# anambe_azul.net
KiCad netlist of a schematic drawn in EAGLE
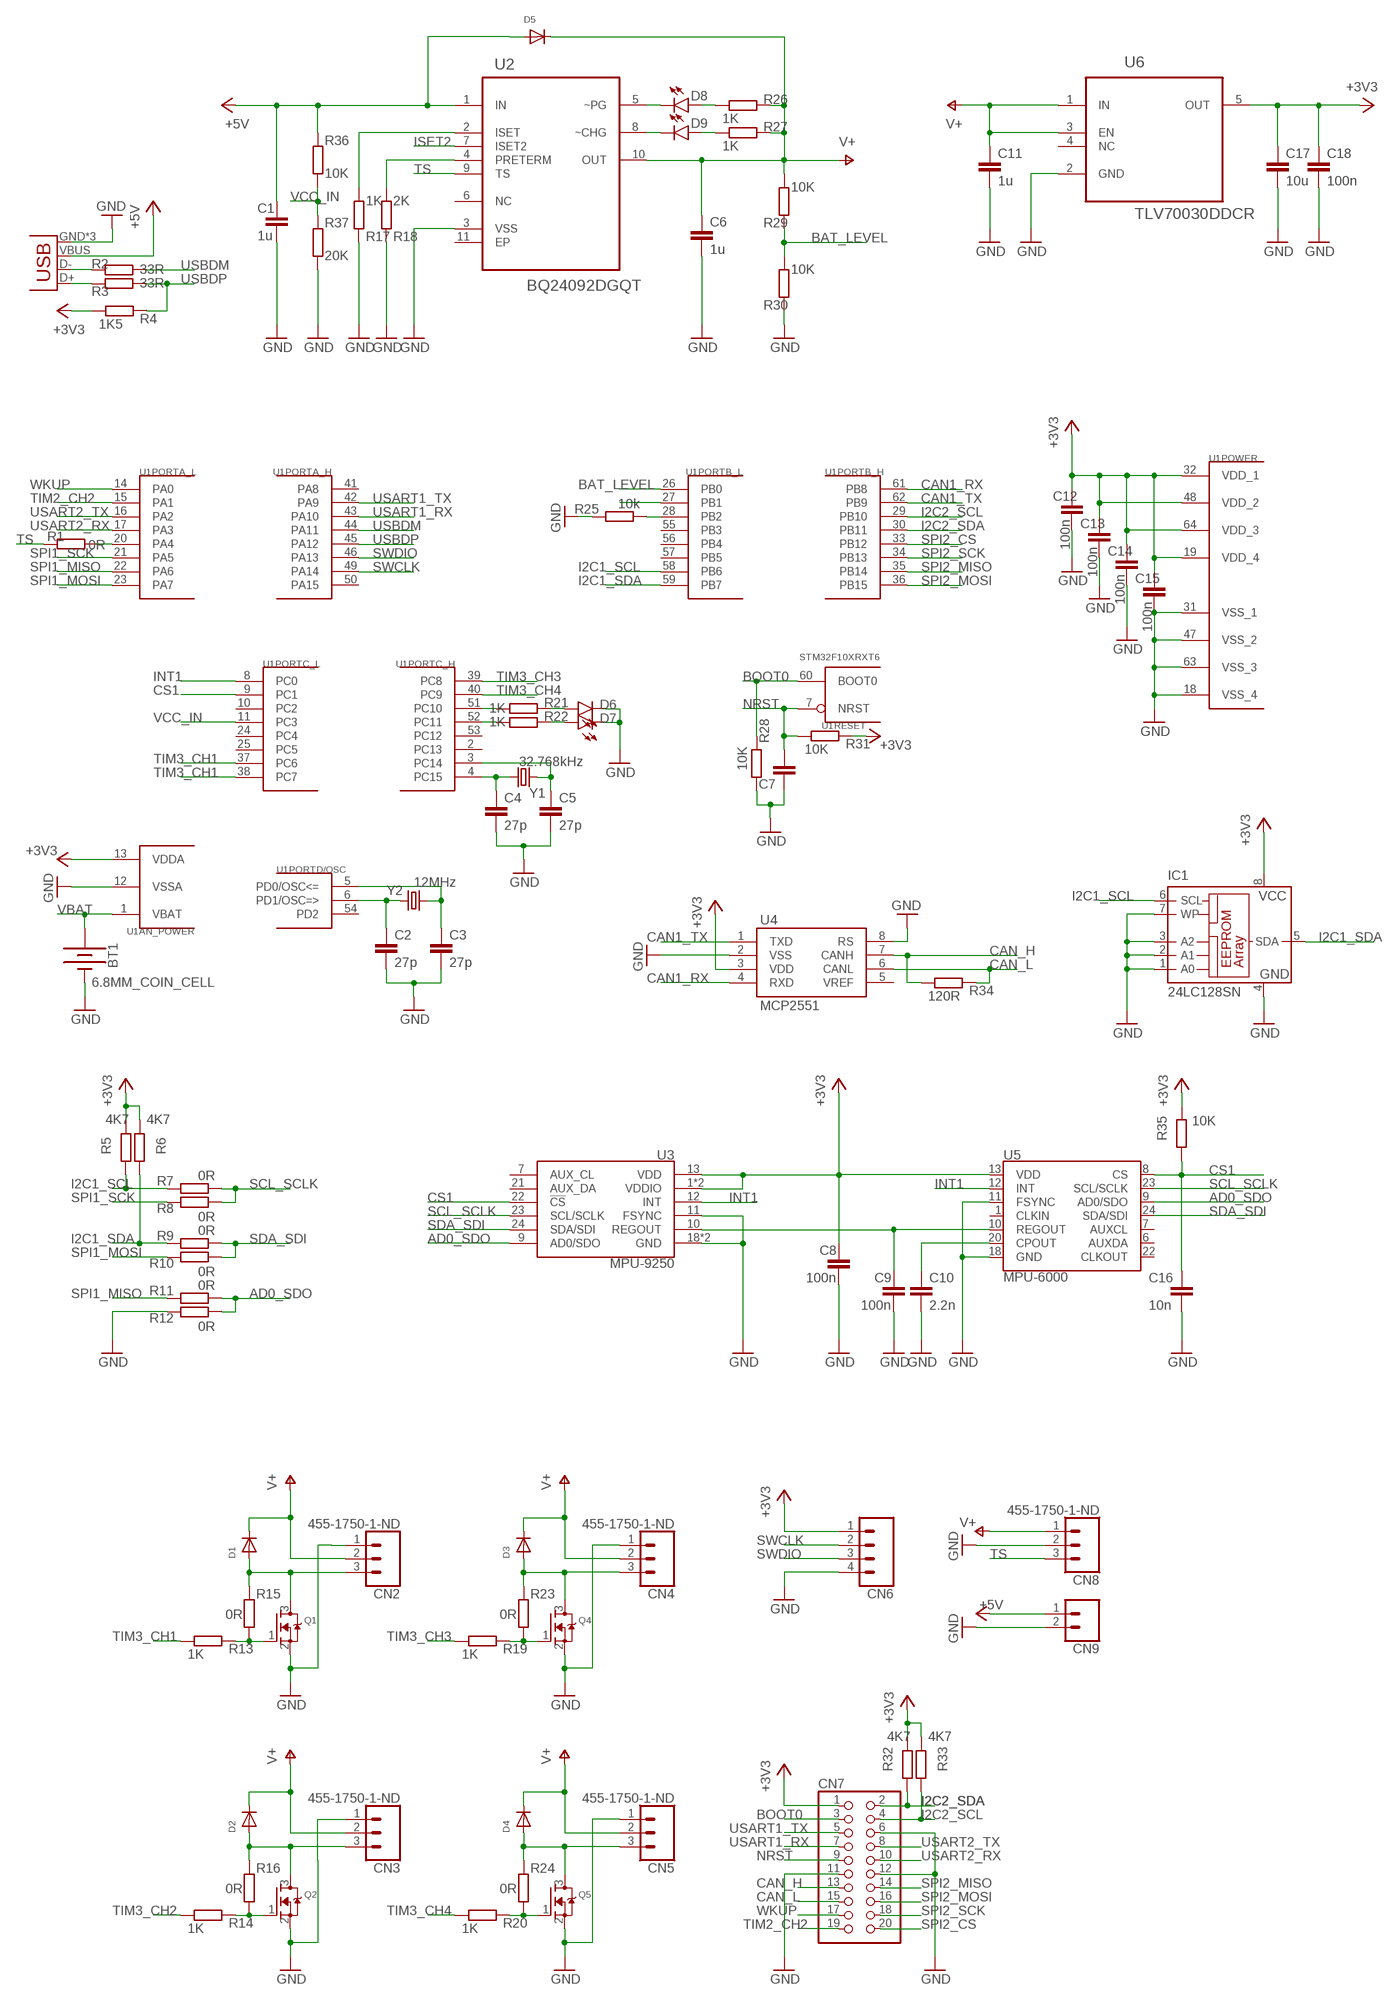
[diagram p0: schematic, sheet 1]

(export (version "E")
  (design (tool "Eeschema 10.0.6"))
  (components
    (comp (ref "BT1")
      (value "6.8MM_COIN_CELL")
      (footprint "eagle-import:BATTCON-6.8MM")
      (libsource (lib "eagle-import") (part "BATTERY-6.8MM_SMD"))
    )
    (comp (ref "C1")
      (value "1u")
      (footprint "eagle-import:C0603")
      (libsource (lib "eagle-import") (part "C-EUC0603"))
    )
    (comp (ref "C2")
      (value "27p")
      (footprint "eagle-import:C0603")
      (libsource (lib "eagle-import") (part "C-EUC0603"))
    )
    (comp (ref "C3")
      (value "27p")
      (footprint "eagle-import:C0603")
      (libsource (lib "eagle-import") (part "C-EUC0603"))
    )
    (comp (ref "C4")
      (value "27p")
      (footprint "eagle-import:C0603")
      (libsource (lib "eagle-import") (part "C-EUC0603"))
    )
    (comp (ref "C5")
      (value "27p")
      (footprint "eagle-import:C0603")
      (libsource (lib "eagle-import") (part "C-EUC0603"))
    )
    (comp (ref "C6")
      (value "1u")
      (footprint "eagle-import:C0603")
      (libsource (lib "eagle-import") (part "C-EUC0603"))
    )
    (comp (ref "C7")
      (value "C-EUC0603")
      (footprint "eagle-import:C0603")
      (libsource (lib "eagle-import") (part "C-EUC0603"))
    )
    (comp (ref "C8")
      (value "100n")
      (footprint "eagle-import:C0603")
      (libsource (lib "eagle-import") (part "C-EUC0603"))
    )
    (comp (ref "C9")
      (value "100n")
      (footprint "eagle-import:C0603")
      (libsource (lib "eagle-import") (part "C-EUC0603"))
    )
    (comp (ref "C10")
      (value "2.2n")
      (footprint "eagle-import:C0603")
      (libsource (lib "eagle-import") (part "C-EUC0603"))
    )
    (comp (ref "C11")
      (value "1u")
      (footprint "eagle-import:C0603")
      (libsource (lib "eagle-import") (part "C-EUC0603"))
    )
    (comp (ref "C12")
      (value "100n")
      (footprint "eagle-import:C0603")
      (libsource (lib "eagle-import") (part "C-EUC0603"))
    )
    (comp (ref "C13")
      (value "100n")
      (footprint "eagle-import:C0603")
      (libsource (lib "eagle-import") (part "C-EUC0603"))
    )
    (comp (ref "C14")
      (value "100n")
      (footprint "eagle-import:C0603")
      (libsource (lib "eagle-import") (part "C-EUC0603"))
    )
    (comp (ref "C15")
      (value "100n")
      (footprint "eagle-import:C0603")
      (libsource (lib "eagle-import") (part "C-EUC0603"))
    )
    (comp (ref "C16")
      (value "10n")
      (footprint "eagle-import:C0603")
      (libsource (lib "eagle-import") (part "C-EUC0603"))
    )
    (comp (ref "C17")
      (value "10u")
      (footprint "eagle-import:C0603")
      (libsource (lib "eagle-import") (part "C-EUC0603"))
    )
    (comp (ref "C18")
      (value "100n")
      (footprint "eagle-import:C0603")
      (libsource (lib "eagle-import") (part "C-EUC0603"))
    )
    (comp (ref "CN1")
      (value "SPARKFUN-CONNECTORS_USB-MICROB")
      (footprint "eagle-import:SPARKFUN-CONNECTORS_USB-MICROB")
      (libsource (lib "eagle-import") (part "SPARKFUN-CONNECTORS_USB-MICROB"))
    )
    (comp (ref "CN2")
      (value "455-1750-1-ND")
      (footprint "eagle-import:1X03")
      (libsource (lib "eagle-import") (part "CONN_03"))
    )
    (comp (ref "CN3")
      (value "455-1750-1-ND")
      (footprint "eagle-import:1X03")
      (libsource (lib "eagle-import") (part "CONN_03"))
    )
    (comp (ref "CN4")
      (value "455-1750-1-ND")
      (footprint "eagle-import:1X03")
      (libsource (lib "eagle-import") (part "CONN_03"))
    )
    (comp (ref "CN5")
      (value "455-1750-1-ND")
      (footprint "eagle-import:1X03")
      (libsource (lib "eagle-import") (part "CONN_03"))
    )
    (comp (ref "CN6")
      (value "CONN_04")
      (footprint "eagle-import:1X04")
      (libsource (lib "eagle-import") (part "CONN_04"))
    )
    (comp (ref "CN7")
      (value "PINHD-2X10")
      (footprint "eagle-import:2X10")
      (libsource (lib "eagle-import") (part "PINHD-2X10"))
    )
    (comp (ref "CN8")
      (value "455-1750-1-ND")
      (footprint "eagle-import:1X03")
      (libsource (lib "eagle-import") (part "CONN_03"))
    )
    (comp (ref "CN9")
      (value "CONN_02")
      (footprint "eagle-import:1X02")
      (libsource (lib "eagle-import") (part "CONN_02"))
    )
    (comp (ref "D1")
      (value "DIODESOD-123")
      (footprint "eagle-import:SOD-123")
      (libsource (lib "eagle-import") (part "DIODESOD-123"))
    )
    (comp (ref "D2")
      (value "DIODESOD-123")
      (footprint "eagle-import:SOD-123")
      (libsource (lib "eagle-import") (part "DIODESOD-123"))
    )
    (comp (ref "D3")
      (value "DIODESOD-123")
      (footprint "eagle-import:SOD-123")
      (libsource (lib "eagle-import") (part "DIODESOD-123"))
    )
    (comp (ref "D4")
      (value "DIODESOD-123")
      (footprint "eagle-import:SOD-123")
      (libsource (lib "eagle-import") (part "DIODESOD-123"))
    )
    (comp (ref "D5")
      (value "DIODESOD-123")
      (footprint "eagle-import:SOD-123")
      (libsource (lib "eagle-import") (part "DIODESOD-123"))
    )
    (comp (ref "D6")
      (value "LED0603")
      (footprint "eagle-import:LED-0603")
      (libsource (lib "eagle-import") (part "LED0603"))
    )
    (comp (ref "D7")
      (value "LED0603")
      (footprint "eagle-import:LED-0603")
      (libsource (lib "eagle-import") (part "LED0603"))
    )
    (comp (ref "D8")
      (value "LED0603")
      (footprint "eagle-import:LED-0603")
      (libsource (lib "eagle-import") (part "LED0603"))
    )
    (comp (ref "D9")
      (value "LED0603")
      (footprint "eagle-import:LED-0603")
      (libsource (lib "eagle-import") (part "LED0603"))
    )
    (comp (ref "IC1")
      (value "24LC128SN")
      (footprint "eagle-import:SO-08")
      (fields (field (name "MF") "MICROCHIP") (field (name "MPN") "24LC128-I/SNG"))
      (libsource (lib "eagle-import") (part "24SNLC128"))
    )
    (comp (ref "Q1")
      (value "MOSFET-NREFLOW")
      (footprint "eagle-import:SOT23")
      (libsource (lib "eagle-import") (part "MOSFET-NREFLOW"))
    )
    (comp (ref "Q2")
      (value "MOSFET-NREFLOW")
      (footprint "eagle-import:SOT23")
      (libsource (lib "eagle-import") (part "MOSFET-NREFLOW"))
    )
    (comp (ref "Q4")
      (value "MOSFET-NREFLOW")
      (footprint "eagle-import:SOT23")
      (libsource (lib "eagle-import") (part "MOSFET-NREFLOW"))
    )
    (comp (ref "Q5")
      (value "MOSFET-NREFLOW")
      (footprint "eagle-import:SOT23")
      (libsource (lib "eagle-import") (part "MOSFET-NREFLOW"))
    )
    (comp (ref "R1")
      (value "0R")
      (footprint "eagle-import:R0603")
      (libsource (lib "eagle-import") (part "R-EU_R0603"))
    )
    (comp (ref "R2")
      (value "33R")
      (footprint "eagle-import:R0603")
      (libsource (lib "eagle-import") (part "R-EU_R0603"))
    )
    (comp (ref "R3")
      (value "33R")
      (footprint "eagle-import:R0603")
      (libsource (lib "eagle-import") (part "R-EU_R0603"))
    )
    (comp (ref "R4")
      (value "1K5")
      (footprint "eagle-import:R0603")
      (libsource (lib "eagle-import") (part "R-EU_R0603"))
    )
    (comp (ref "R5")
      (value "4K7")
      (footprint "eagle-import:R0603")
      (libsource (lib "eagle-import") (part "R-EU_R0603"))
    )
    (comp (ref "R6")
      (value "4K7")
      (footprint "eagle-import:R0603")
      (libsource (lib "eagle-import") (part "R-EU_R0603"))
    )
    (comp (ref "R7")
      (value "0R")
      (footprint "eagle-import:R0603")
      (libsource (lib "eagle-import") (part "R-EU_R0603"))
    )
    (comp (ref "R8")
      (value "0R")
      (footprint "eagle-import:R0603")
      (libsource (lib "eagle-import") (part "R-EU_R0603"))
    )
    (comp (ref "R9")
      (value "0R")
      (footprint "eagle-import:R0603")
      (libsource (lib "eagle-import") (part "R-EU_R0603"))
    )
    (comp (ref "R10")
      (value "0R")
      (footprint "eagle-import:R0603")
      (libsource (lib "eagle-import") (part "R-EU_R0603"))
    )
    (comp (ref "R11")
      (value "0R")
      (footprint "eagle-import:R0603")
      (libsource (lib "eagle-import") (part "R-EU_R0603"))
    )
    (comp (ref "R12")
      (value "0R")
      (footprint "eagle-import:R0603")
      (libsource (lib "eagle-import") (part "R-EU_R0603"))
    )
    (comp (ref "R13")
      (value "1K")
      (footprint "eagle-import:R0603")
      (libsource (lib "eagle-import") (part "R-EU_R0603"))
    )
    (comp (ref "R14")
      (value "1K")
      (footprint "eagle-import:R0603")
      (libsource (lib "eagle-import") (part "R-EU_R0603"))
    )
    (comp (ref "R15")
      (value "0R")
      (footprint "eagle-import:R0603")
      (libsource (lib "eagle-import") (part "R-EU_R0603"))
    )
    (comp (ref "R16")
      (value "0R")
      (footprint "eagle-import:R0603")
      (libsource (lib "eagle-import") (part "R-EU_R0603"))
    )
    (comp (ref "R17")
      (value "1K")
      (footprint "eagle-import:R0603")
      (libsource (lib "eagle-import") (part "R-EU_R0603"))
    )
    (comp (ref "R18")
      (value "2K")
      (footprint "eagle-import:R0603")
      (libsource (lib "eagle-import") (part "R-EU_R0603"))
    )
    (comp (ref "R19")
      (value "1K")
      (footprint "eagle-import:R0603")
      (libsource (lib "eagle-import") (part "R-EU_R0603"))
    )
    (comp (ref "R20")
      (value "1K")
      (footprint "eagle-import:R0603")
      (libsource (lib "eagle-import") (part "R-EU_R0603"))
    )
    (comp (ref "R21")
      (value "1K")
      (footprint "eagle-import:R0603")
      (libsource (lib "eagle-import") (part "R-EU_R0603"))
    )
    (comp (ref "R22")
      (value "1K")
      (footprint "eagle-import:R0603")
      (libsource (lib "eagle-import") (part "R-EU_R0603"))
    )
    (comp (ref "R23")
      (value "0R")
      (footprint "eagle-import:R0603")
      (libsource (lib "eagle-import") (part "R-EU_R0603"))
    )
    (comp (ref "R24")
      (value "0R")
      (footprint "eagle-import:R0603")
      (libsource (lib "eagle-import") (part "R-EU_R0603"))
    )
    (comp (ref "R25")
      (value "10k")
      (footprint "eagle-import:R0603")
      (libsource (lib "eagle-import") (part "R-EU_R0603"))
    )
    (comp (ref "R26")
      (value "1K")
      (footprint "eagle-import:R0603")
      (libsource (lib "eagle-import") (part "R-EU_R0603"))
    )
    (comp (ref "R27")
      (value "1K")
      (footprint "eagle-import:R0603")
      (libsource (lib "eagle-import") (part "R-EU_R0603"))
    )
    (comp (ref "R28")
      (value "10K")
      (footprint "eagle-import:R0603")
      (libsource (lib "eagle-import") (part "R-EU_R0603"))
    )
    (comp (ref "R29")
      (value "10K")
      (footprint "eagle-import:R0603")
      (libsource (lib "eagle-import") (part "R-EU_R0603"))
    )
    (comp (ref "R30")
      (value "10K")
      (footprint "eagle-import:R0603")
      (libsource (lib "eagle-import") (part "R-EU_R0603"))
    )
    (comp (ref "R31")
      (value "10K")
      (footprint "eagle-import:R0603")
      (libsource (lib "eagle-import") (part "R-EU_R0603"))
    )
    (comp (ref "R32")
      (value "4K7")
      (footprint "eagle-import:R0603")
      (libsource (lib "eagle-import") (part "R-EU_R0603"))
    )
    (comp (ref "R33")
      (value "4K7")
      (footprint "eagle-import:R0603")
      (libsource (lib "eagle-import") (part "R-EU_R0603"))
    )
    (comp (ref "R34")
      (value "120R")
      (footprint "eagle-import:R0603")
      (libsource (lib "eagle-import") (part "R-EU_R0603"))
    )
    (comp (ref "R35")
      (value "10K")
      (footprint "eagle-import:R0603")
      (libsource (lib "eagle-import") (part "R-EU_R0603"))
    )
    (comp (ref "R36")
      (value "10K")
      (footprint "eagle-import:R0603")
      (libsource (lib "eagle-import") (part "R-EU_R0603"))
    )
    (comp (ref "R37")
      (value "20K")
      (footprint "eagle-import:R0603")
      (libsource (lib "eagle-import") (part "R-EU_R0603"))
    )
    (comp (ref "U1")
      (value "STM32F10XRXT6")
      (footprint "eagle-import:TQFP64")
      (libsource (lib "eagle-import") (part "STM32F10XRXT6"))
    )
    (comp (ref "U2")
      (value "BQ24092DGQT")
      (footprint "eagle-import:SOP50P490X110-11N")
      (libsource (lib "eagle-import") (part "BQ24092DGQT"))
    )
    (comp (ref "U3")
      (value "MPU-9250")
      (footprint "eagle-import:QFN24-3X3")
      (libsource (lib "eagle-import") (part "MPU-9250"))
    )
    (comp (ref "U4")
      (value "MCP2551")
      (footprint "eagle-import:SO08")
      (libsource (lib "eagle-import") (part "MCP2551"))
    )
    (comp (ref "U5")
      (value "MPU-6000")
      (footprint "eagle-import:QFN-24-EP")
      (libsource (lib "eagle-import") (part "MPU-6000"))
    )
    (comp (ref "U6")
      (value "TLV70030DDCR")
      (footprint "eagle-import:SOT95P280X110-5N")
      (libsource (lib "eagle-import") (part "TLV70030DDCR"))
    )
    (comp (ref "Y1")
      (value "32.768kHz")
      (footprint "eagle-import:CRYSTAL-PTH-2X6-CYL")
      (libsource (lib "eagle-import") (part "CRYSTAL-32.768KHZPTH-2X6"))
    )
    (comp (ref "Y2")
      (value "12MHz")
      (footprint "eagle-import:HC49UP")
      (libsource (lib "eagle-import") (part "CRYSTALHC49UP"))
    )
  )
  (nets
    (net (code "1") (name "+3V3") (class "Default")
      (node (ref "C12") (pin "1") (pinfunction "1_1") (pintype "passive"))
      (node (ref "C13") (pin "1") (pinfunction "1_1") (pintype "passive"))
      (node (ref "C14") (pin "1") (pinfunction "1_1") (pintype "passive"))
      (node (ref "C15") (pin "1") (pinfunction "1_1") (pintype "passive"))
      (node (ref "C17") (pin "1") (pinfunction "1_1") (pintype "passive"))
      (node (ref "C18") (pin "1") (pinfunction "1_1") (pintype "passive"))
      (node (ref "C8") (pin "1") (pinfunction "1_1") (pintype "passive"))
      (node (ref "CN6") (pin "1") (pinfunction "1_1") (pintype "passive"))
      (node (ref "CN7") (pin "1") (pinfunction "1_1") (pintype "passive"))
      (node (ref "IC1") (pin "8") (pinfunction "VCC_8") (pintype "power_in"))
      (node (ref "R31") (pin "2") (pinfunction "2_2") (pintype "passive"))
      (node (ref "R32") (pin "1") (pinfunction "1_1") (pintype "passive"))
      (node (ref "R33") (pin "1") (pinfunction "1_1") (pintype "passive"))
      (node (ref "R35") (pin "2") (pinfunction "2_2") (pintype "passive"))
      (node (ref "R4") (pin "1") (pinfunction "1_1") (pintype "passive"))
      (node (ref "R5") (pin "1") (pinfunction "1_1") (pintype "passive"))
      (node (ref "R6") (pin "1") (pinfunction "1_1") (pintype "passive"))
      (node (ref "U1") (pin "13") (pinfunction "VDDA_13") (pintype "power_in"))
      (node (ref "U1") (pin "19") (pinfunction "VDD_4_19") (pintype "power_in"))
      (node (ref "U1") (pin "32") (pinfunction "VDD_1_32") (pintype "power_in"))
      (node (ref "U1") (pin "48") (pinfunction "VDD_2_48") (pintype "power_in"))
      (node (ref "U1") (pin "64") (pinfunction "VDD_3_64") (pintype "power_in"))
      (node (ref "U3") (pin "1") (pinfunction "VDDIO_1") (pintype "bidirectional"))
      (node (ref "U3") (pin "13") (pinfunction "VDD_13") (pintype "bidirectional"))
      (node (ref "U3") (pin "8") (pinfunction "VDDIO_8") (pintype "bidirectional"))
      (node (ref "U4") (pin "3") (pinfunction "VDD_3") (pintype "bidirectional"))
      (node (ref "U5") (pin "13") (pinfunction "VDD_13") (pintype "bidirectional"))
      (node (ref "U6") (pin "5") (pinfunction "OUT_5") (pintype "output"))
    )
    (net (code "2") (name "+5V") (class "Default")
      (node (ref "C1") (pin "1") (pinfunction "1_1") (pintype "passive"))
      (node (ref "CN1") (pin "VBUS") (pinfunction "VBUS_VBUS") (pintype "bidirectional"))
      (node (ref "CN9") (pin "1") (pinfunction "1_1") (pintype "passive"))
      (node (ref "D5") (pin "A") (pinfunction "A_A") (pintype "passive"))
      (node (ref "R36") (pin "2") (pinfunction "2_2") (pintype "passive"))
      (node (ref "U2") (pin "1") (pinfunction "IN_1") (pintype "power_in"))
    )
    (net (code "3") (name "/AD0_SDO") (class "Default")
      (node (ref "R11") (pin "1") (pinfunction "1_1") (pintype "passive"))
      (node (ref "R12") (pin "1") (pinfunction "1_1") (pintype "passive"))
      (node (ref "U3") (pin "9") (pinfunction "AD0/SDO_9") (pintype "bidirectional"))
      (node (ref "U5") (pin "9") (pinfunction "AD0/SDO_9") (pintype "bidirectional"))
    )
    (net (code "4") (name "/BAT_LEVEL") (class "Default")
      (node (ref "R29") (pin "2") (pinfunction "2_2") (pintype "passive"))
      (node (ref "R30") (pin "1") (pinfunction "1_1") (pintype "passive"))
      (node (ref "U1") (pin "26") (pinfunction "PB0_26") (pintype "bidirectional"))
    )
    (net (code "5") (name "/BOOT0") (class "Default")
      (node (ref "CN7") (pin "3") (pinfunction "3_3") (pintype "passive"))
      (node (ref "R28") (pin "2") (pinfunction "2_2") (pintype "passive"))
      (node (ref "U1") (pin "60") (pinfunction "BOOT0_60") (pintype "input"))
    )
    (net (code "6") (name "/CAN1_RX") (class "Default")
      (node (ref "U1") (pin "61") (pinfunction "PB8_61") (pintype "bidirectional"))
      (node (ref "U4") (pin "4") (pinfunction "RXD_4") (pintype "bidirectional"))
    )
    (net (code "7") (name "/CAN1_TX") (class "Default")
      (node (ref "U1") (pin "62") (pinfunction "PB9_62") (pintype "bidirectional"))
      (node (ref "U4") (pin "1") (pinfunction "TXD_1") (pintype "bidirectional"))
    )
    (net (code "8") (name "/CAN_H") (class "Default")
      (node (ref "CN7") (pin "13") (pinfunction "13_13") (pintype "passive"))
      (node (ref "R34") (pin "1") (pinfunction "1_1") (pintype "passive"))
      (node (ref "U4") (pin "7") (pinfunction "CANH_7") (pintype "bidirectional"))
    )
    (net (code "9") (name "/CAN_L") (class "Default")
      (node (ref "CN7") (pin "15") (pinfunction "15_15") (pintype "passive"))
      (node (ref "R34") (pin "2") (pinfunction "2_2") (pintype "passive"))
      (node (ref "U4") (pin "6") (pinfunction "CANL_6") (pintype "bidirectional"))
    )
    (net (code "10") (name "/CS1") (class "Default")
      (node (ref "C16") (pin "1") (pinfunction "1_1") (pintype "passive"))
      (node (ref "R35") (pin "1") (pinfunction "1_1") (pintype "passive"))
      (node (ref "U1") (pin "9") (pinfunction "PC1_9") (pintype "bidirectional"))
      (node (ref "U3") (pin "22") (pinfunction "~{CS}_22") (pintype "bidirectional"))
      (node (ref "U5") (pin "8") (pinfunction "CS_8") (pintype "bidirectional"))
    )
    (net (code "11") (name "/I2C1_SCL") (class "Default")
      (node (ref "IC1") (pin "6") (pinfunction "SCL_6") (pintype "input"))
      (node (ref "R5") (pin "2") (pinfunction "2_2") (pintype "passive"))
      (node (ref "R7") (pin "2") (pinfunction "2_2") (pintype "passive"))
      (node (ref "U1") (pin "58") (pinfunction "PB6_58") (pintype "bidirectional"))
    )
    (net (code "12") (name "/I2C1_SDA") (class "Default")
      (node (ref "IC1") (pin "5") (pinfunction "SDA_5") (pintype "bidirectional"))
      (node (ref "R6") (pin "2") (pinfunction "2_2") (pintype "passive"))
      (node (ref "R9") (pin "2") (pinfunction "2_2") (pintype "passive"))
      (node (ref "U1") (pin "59") (pinfunction "PB7_59") (pintype "bidirectional"))
    )
    (net (code "13") (name "/I2C2_SCL") (class "Default")
      (node (ref "CN7") (pin "4") (pinfunction "4_4") (pintype "passive"))
      (node (ref "R33") (pin "2") (pinfunction "2_2") (pintype "passive"))
      (node (ref "U1") (pin "29") (pinfunction "PB10_29") (pintype "bidirectional"))
    )
    (net (code "14") (name "/I2C2_SDA") (class "Default")
      (node (ref "CN7") (pin "2") (pinfunction "2_2") (pintype "passive"))
      (node (ref "R32") (pin "2") (pinfunction "2_2") (pintype "passive"))
      (node (ref "U1") (pin "30") (pinfunction "PB11_30") (pintype "bidirectional"))
    )
    (net (code "15") (name "/INT1") (class "Default")
      (node (ref "U1") (pin "8") (pinfunction "PC0_8") (pintype "bidirectional"))
      (node (ref "U3") (pin "12") (pinfunction "INT_12") (pintype "bidirectional"))
      (node (ref "U5") (pin "12") (pinfunction "INT_12") (pintype "bidirectional"))
    )
    (net (code "16") (name "/ISET2") (class "Default")
      (node (ref "U1") (pin "27") (pinfunction "PB1_27") (pintype "bidirectional"))
      (node (ref "U2") (pin "7") (pinfunction "ISET2_7") (pintype "input"))
    )
    (net (code "17") (name "/NRST") (class "Default")
      (node (ref "C7") (pin "2") (pinfunction "2_2") (pintype "passive"))
      (node (ref "CN7") (pin "9") (pinfunction "9_9") (pintype "passive"))
      (node (ref "R31") (pin "1") (pinfunction "1_1") (pintype "passive"))
      (node (ref "U1") (pin "7") (pinfunction "NRST_7") (pintype "input"))
    )
    (net (code "18") (name "/SCL_SCLK") (class "Default")
      (node (ref "R7") (pin "1") (pinfunction "1_1") (pintype "passive"))
      (node (ref "R8") (pin "1") (pinfunction "1_1") (pintype "passive"))
      (node (ref "U3") (pin "23") (pinfunction "SCL/SCLK_23") (pintype "bidirectional"))
      (node (ref "U5") (pin "23") (pinfunction "SCL/SCLK_23") (pintype "bidirectional"))
    )
    (net (code "19") (name "/SDA_SDI") (class "Default")
      (node (ref "R10") (pin "1") (pinfunction "1_1") (pintype "passive"))
      (node (ref "R9") (pin "1") (pinfunction "1_1") (pintype "passive"))
      (node (ref "U3") (pin "24") (pinfunction "SDA/SDI_24") (pintype "bidirectional"))
      (node (ref "U5") (pin "24") (pinfunction "SDA/SDI_24") (pintype "bidirectional"))
    )
    (net (code "20") (name "/SPI1_MISO") (class "Default")
      (node (ref "R11") (pin "2") (pinfunction "2_2") (pintype "passive"))
      (node (ref "U1") (pin "22") (pinfunction "PA6_22") (pintype "bidirectional"))
    )
    (net (code "21") (name "/SPI1_MOSI") (class "Default")
      (node (ref "R10") (pin "2") (pinfunction "2_2") (pintype "passive"))
      (node (ref "U1") (pin "23") (pinfunction "PA7_23") (pintype "bidirectional"))
    )
    (net (code "22") (name "/SPI1_SCK") (class "Default")
      (node (ref "R8") (pin "2") (pinfunction "2_2") (pintype "passive"))
      (node (ref "U1") (pin "21") (pinfunction "PA5_21") (pintype "bidirectional"))
    )
    (net (code "23") (name "/SPI2_CS") (class "Default")
      (node (ref "CN7") (pin "20") (pinfunction "20_20") (pintype "passive"))
      (node (ref "U1") (pin "33") (pinfunction "PB12_33") (pintype "bidirectional"))
    )
    (net (code "24") (name "/SPI2_MISO") (class "Default")
      (node (ref "CN7") (pin "14") (pinfunction "14_14") (pintype "passive"))
      (node (ref "U1") (pin "35") (pinfunction "PB14_35") (pintype "bidirectional"))
    )
    (net (code "25") (name "/SPI2_MOSI") (class "Default")
      (node (ref "CN7") (pin "16") (pinfunction "16_16") (pintype "passive"))
      (node (ref "U1") (pin "36") (pinfunction "PB15_36") (pintype "bidirectional"))
    )
    (net (code "26") (name "/SPI2_SCK") (class "Default")
      (node (ref "CN7") (pin "18") (pinfunction "18_18") (pintype "passive"))
      (node (ref "U1") (pin "34") (pinfunction "PB13_34") (pintype "bidirectional"))
    )
    (net (code "27") (name "/SWCLK") (class "Default")
      (node (ref "CN6") (pin "2") (pinfunction "2_2") (pintype "passive"))
      (node (ref "U1") (pin "49") (pinfunction "PA14_49") (pintype "bidirectional"))
    )
    (net (code "28") (name "/SWDIO") (class "Default")
      (node (ref "CN6") (pin "3") (pinfunction "3_3") (pintype "passive"))
      (node (ref "U1") (pin "46") (pinfunction "PA13_46") (pintype "bidirectional"))
    )
    (net (code "29") (name "/TIM2_CH2") (class "Default")
      (node (ref "CN7") (pin "19") (pinfunction "19_19") (pintype "passive"))
      (node (ref "U1") (pin "15") (pinfunction "PA1_15") (pintype "bidirectional"))
    )
    (net (code "30") (name "/TIM3_CH1") (class "Default")
      (node (ref "R13") (pin "1") (pinfunction "1_1") (pintype "passive"))
      (node (ref "U1") (pin "37") (pinfunction "PC6_37") (pintype "bidirectional"))
    )
    (net (code "31") (name "/TIM3_CH2") (class "Default")
      (node (ref "R14") (pin "1") (pinfunction "1_1") (pintype "passive"))
      (node (ref "U1") (pin "38") (pinfunction "PC7_38") (pintype "bidirectional"))
    )
    (net (code "32") (name "/TIM3_CH3") (class "Default")
      (node (ref "R19") (pin "1") (pinfunction "1_1") (pintype "passive"))
      (node (ref "U1") (pin "39") (pinfunction "PC8_39") (pintype "bidirectional"))
    )
    (net (code "33") (name "/TIM3_CH4") (class "Default")
      (node (ref "R20") (pin "1") (pinfunction "1_1") (pintype "passive"))
      (node (ref "U1") (pin "40") (pinfunction "PC9_40") (pintype "bidirectional"))
    )
    (net (code "34") (name "/TS") (class "Default")
      (node (ref "CN8") (pin "3") (pinfunction "3_3") (pintype "passive"))
      (node (ref "R1") (pin "2") (pinfunction "2_2") (pintype "passive"))
      (node (ref "U2") (pin "9") (pinfunction "TS_9") (pintype "input"))
    )
    (net (code "35") (name "/USART1_RX") (class "Default")
      (node (ref "CN7") (pin "7") (pinfunction "7_7") (pintype "passive"))
      (node (ref "U1") (pin "43") (pinfunction "PA10_43") (pintype "bidirectional"))
    )
    (net (code "36") (name "/USART1_TX") (class "Default")
      (node (ref "CN7") (pin "5") (pinfunction "5_5") (pintype "passive"))
      (node (ref "U1") (pin "42") (pinfunction "PA9_42") (pintype "bidirectional"))
    )
    (net (code "37") (name "/USART2_RX") (class "Default")
      (node (ref "CN7") (pin "10") (pinfunction "10_10") (pintype "passive"))
      (node (ref "U1") (pin "17") (pinfunction "PA3_17") (pintype "bidirectional"))
    )
    (net (code "38") (name "/USART2_TX") (class "Default")
      (node (ref "CN7") (pin "8") (pinfunction "8_8") (pintype "passive"))
      (node (ref "U1") (pin "16") (pinfunction "PA2_16") (pintype "bidirectional"))
    )
    (net (code "39") (name "/USBDM") (class "Default")
      (node (ref "R2") (pin "2") (pinfunction "2_2") (pintype "passive"))
      (node (ref "U1") (pin "44") (pinfunction "PA11_44") (pintype "bidirectional"))
    )
    (net (code "40") (name "/USBDP") (class "Default")
      (node (ref "R3") (pin "2") (pinfunction "2_2") (pintype "passive"))
      (node (ref "R4") (pin "2") (pinfunction "2_2") (pintype "passive"))
      (node (ref "U1") (pin "45") (pinfunction "PA12_45") (pintype "bidirectional"))
    )
    (net (code "41") (name "/VBAT") (class "Default")
      (node (ref "BT1") (pin "+") (pinfunction "+_+") (pintype "power_in"))
      (node (ref "U1") (pin "1") (pinfunction "VBAT_1") (pintype "power_in"))
    )
    (net (code "42") (name "/VCC_IN") (class "Default")
      (node (ref "R36") (pin "1") (pinfunction "1_1") (pintype "passive"))
      (node (ref "R37") (pin "1") (pinfunction "1_1") (pintype "passive"))
      (node (ref "U1") (pin "11") (pinfunction "PC3_11") (pintype "bidirectional"))
    )
    (net (code "43") (name "/WKUP") (class "Default")
      (node (ref "CN7") (pin "17") (pinfunction "17_17") (pintype "passive"))
      (node (ref "U1") (pin "14") (pinfunction "PA0_14") (pintype "bidirectional"))
    )
    (net (code "44") (name "GND") (class "Default")
      (node (ref "BT1") (pin "-") (pinfunction "-_-") (pintype "power_in"))
      (node (ref "C1") (pin "2") (pinfunction "2_2") (pintype "passive"))
      (node (ref "C10") (pin "2") (pinfunction "2_2") (pintype "passive"))
      (node (ref "C11") (pin "2") (pinfunction "2_2") (pintype "passive"))
      (node (ref "C12") (pin "2") (pinfunction "2_2") (pintype "passive"))
      (node (ref "C13") (pin "2") (pinfunction "2_2") (pintype "passive"))
      (node (ref "C14") (pin "2") (pinfunction "2_2") (pintype "passive"))
      (node (ref "C15") (pin "2") (pinfunction "2_2") (pintype "passive"))
      (node (ref "C16") (pin "2") (pinfunction "2_2") (pintype "passive"))
      (node (ref "C17") (pin "2") (pinfunction "2_2") (pintype "passive"))
      (node (ref "C18") (pin "2") (pinfunction "2_2") (pintype "passive"))
      (node (ref "C2") (pin "2") (pinfunction "2_2") (pintype "passive"))
      (node (ref "C3") (pin "2") (pinfunction "2_2") (pintype "passive"))
      (node (ref "C4") (pin "2") (pinfunction "2_2") (pintype "passive"))
      (node (ref "C5") (pin "2") (pinfunction "2_2") (pintype "passive"))
      (node (ref "C6") (pin "2") (pinfunction "2_2") (pintype "passive"))
      (node (ref "C7") (pin "1") (pinfunction "1_1") (pintype "passive"))
      (node (ref "C8") (pin "2") (pinfunction "2_2") (pintype "passive"))
      (node (ref "C9") (pin "2") (pinfunction "2_2") (pintype "passive"))
      (node (ref "CN1") (pin "GND") (pinfunction "GND_GND") (pintype "bidirectional"))
      (node (ref "CN1") (pin "MT1") (pinfunction "GND_MT1") (pintype "bidirectional"))
      (node (ref "CN1") (pin "MT2") (pinfunction "GND_MT2") (pintype "bidirectional"))
      (node (ref "CN2") (pin "1") (pinfunction "1_1") (pintype "passive"))
      (node (ref "CN3") (pin "1") (pinfunction "1_1") (pintype "passive"))
      (node (ref "CN4") (pin "1") (pinfunction "1_1") (pintype "passive"))
      (node (ref "CN5") (pin "1") (pinfunction "1_1") (pintype "passive"))
      (node (ref "CN6") (pin "4") (pinfunction "4_4") (pintype "passive"))
      (node (ref "CN7") (pin "11") (pinfunction "11_11") (pintype "passive"))
      (node (ref "CN7") (pin "12") (pinfunction "12_12") (pintype "passive"))
      (node (ref "CN7") (pin "6") (pinfunction "6_6") (pintype "passive"))
      (node (ref "CN8") (pin "2") (pinfunction "2_2") (pintype "passive"))
      (node (ref "CN9") (pin "2") (pinfunction "2_2") (pintype "passive"))
      (node (ref "D6") (pin "C") (pinfunction "C_C") (pintype "passive"))
      (node (ref "D7") (pin "C") (pinfunction "C_C") (pintype "passive"))
      (node (ref "IC1") (pin "1") (pinfunction "A0_1") (pintype "input"))
      (node (ref "IC1") (pin "2") (pinfunction "A1_2") (pintype "input"))
      (node (ref "IC1") (pin "3") (pinfunction "A2_3") (pintype "input"))
      (node (ref "IC1") (pin "4") (pinfunction "GND_4") (pintype "power_in"))
      (node (ref "IC1") (pin "7") (pinfunction "WP_7") (pintype "input"))
      (node (ref "Q1") (pin "2") (pinfunction "S_2") (pintype "bidirectional"))
      (node (ref "Q2") (pin "2") (pinfunction "S_2") (pintype "bidirectional"))
      (node (ref "Q4") (pin "2") (pinfunction "S_2") (pintype "bidirectional"))
      (node (ref "Q5") (pin "2") (pinfunction "S_2") (pintype "bidirectional"))
      (node (ref "R12") (pin "2") (pinfunction "2_2") (pintype "passive"))
      (node (ref "R17") (pin "2") (pinfunction "2_2") (pintype "passive"))
      (node (ref "R18") (pin "2") (pinfunction "2_2") (pintype "passive"))
      (node (ref "R25") (pin "2") (pinfunction "2_2") (pintype "passive"))
      (node (ref "R28") (pin "1") (pinfunction "1_1") (pintype "passive"))
      (node (ref "R30") (pin "2") (pinfunction "2_2") (pintype "passive"))
      (node (ref "R37") (pin "2") (pinfunction "2_2") (pintype "passive"))
      (node (ref "U1") (pin "12") (pinfunction "VSSA_12") (pintype "power_in"))
      (node (ref "U1") (pin "18") (pinfunction "VSS_4_18") (pintype "power_in"))
      (node (ref "U1") (pin "31") (pinfunction "VSS_1_31") (pintype "power_in"))
      (node (ref "U1") (pin "47") (pinfunction "VSS_2_47") (pintype "power_in"))
      (node (ref "U1") (pin "63") (pinfunction "VSS_3_63") (pintype "power_in"))
      (node (ref "U2") (pin "3") (pinfunction "VSS_3") (pintype "passive"))
      (node (ref "U3") (pin "11") (pinfunction "FSYNC_11") (pintype "bidirectional"))
      (node (ref "U3") (pin "18") (pinfunction "GND_18") (pintype "bidirectional"))
      (node (ref "U3") (pin "20") (pinfunction "GND_20") (pintype "bidirectional"))
      (node (ref "U4") (pin "2") (pinfunction "VSS_2") (pintype "bidirectional"))
      (node (ref "U4") (pin "8") (pinfunction "RS_8") (pintype "bidirectional"))
      (node (ref "U5") (pin "11") (pinfunction "FSYNC_11") (pintype "bidirectional"))
      (node (ref "U5") (pin "18") (pinfunction "GND_18") (pintype "bidirectional"))
      (node (ref "U6") (pin "2") (pinfunction "GND_2") (pintype "passive"))
    )
    (net (code "45") (name "Net-(CN1-PadD+)") (class "Default")
      (node (ref "CN1") (pin "D+") (pinfunction "D+_D+") (pintype "bidirectional"))
      (node (ref "R3") (pin "1") (pinfunction "1_1") (pintype "passive"))
    )
    (net (code "46") (name "Net-(CN1-PadD-)") (class "Default")
      (node (ref "CN1") (pin "D-") (pinfunction "D-_D-") (pintype "bidirectional"))
      (node (ref "R2") (pin "1") (pinfunction "1_1") (pintype "passive"))
    )
    (net (code "47") (name "Net-(D6-PadA)") (class "Default")
      (node (ref "D6") (pin "A") (pinfunction "A_A") (pintype "passive"))
      (node (ref "R21") (pin "2") (pinfunction "2_2") (pintype "passive"))
    )
    (net (code "48") (name "Net-(D7-PadA)") (class "Default")
      (node (ref "D7") (pin "A") (pinfunction "A_A") (pintype "passive"))
      (node (ref "R22") (pin "2") (pinfunction "2_2") (pintype "passive"))
    )
    (net (code "49") (name "Net-(D8-PadA)") (class "Default")
      (node (ref "D8") (pin "A") (pinfunction "A_A") (pintype "passive"))
      (node (ref "R26") (pin "1") (pinfunction "1_1") (pintype "passive"))
    )
    (net (code "50") (name "Net-(D9-PadA)") (class "Default")
      (node (ref "D9") (pin "A") (pinfunction "A_A") (pintype "passive"))
      (node (ref "R27") (pin "1") (pinfunction "1_1") (pintype "passive"))
    )
    (net (code "51") (name "Net-(Q1-D)") (class "Default")
      (node (ref "CN2") (pin "3") (pinfunction "3_3") (pintype "passive"))
      (node (ref "D1") (pin "A") (pinfunction "A_A") (pintype "passive"))
      (node (ref "Q1") (pin "3") (pinfunction "D_3") (pintype "bidirectional"))
      (node (ref "R15") (pin "2") (pinfunction "2_2") (pintype "passive"))
    )
    (net (code "52") (name "Net-(Q1-G)") (class "Default")
      (node (ref "Q1") (pin "1") (pinfunction "G_1") (pintype "bidirectional"))
      (node (ref "R13") (pin "2") (pinfunction "2_2") (pintype "passive"))
      (node (ref "R15") (pin "1") (pinfunction "1_1") (pintype "passive"))
    )
    (net (code "53") (name "Net-(Q2-D)") (class "Default")
      (node (ref "CN3") (pin "3") (pinfunction "3_3") (pintype "passive"))
      (node (ref "D2") (pin "A") (pinfunction "A_A") (pintype "passive"))
      (node (ref "Q2") (pin "3") (pinfunction "D_3") (pintype "bidirectional"))
      (node (ref "R16") (pin "2") (pinfunction "2_2") (pintype "passive"))
    )
    (net (code "54") (name "Net-(Q2-G)") (class "Default")
      (node (ref "Q2") (pin "1") (pinfunction "G_1") (pintype "bidirectional"))
      (node (ref "R14") (pin "2") (pinfunction "2_2") (pintype "passive"))
      (node (ref "R16") (pin "1") (pinfunction "1_1") (pintype "passive"))
    )
    (net (code "55") (name "Net-(Q4-D)") (class "Default")
      (node (ref "CN4") (pin "3") (pinfunction "3_3") (pintype "passive"))
      (node (ref "D3") (pin "A") (pinfunction "A_A") (pintype "passive"))
      (node (ref "Q4") (pin "3") (pinfunction "D_3") (pintype "bidirectional"))
      (node (ref "R23") (pin "2") (pinfunction "2_2") (pintype "passive"))
    )
    (net (code "56") (name "Net-(Q4-G)") (class "Default")
      (node (ref "Q4") (pin "1") (pinfunction "G_1") (pintype "bidirectional"))
      (node (ref "R19") (pin "2") (pinfunction "2_2") (pintype "passive"))
      (node (ref "R23") (pin "1") (pinfunction "1_1") (pintype "passive"))
    )
    (net (code "57") (name "Net-(Q5-D)") (class "Default")
      (node (ref "CN5") (pin "3") (pinfunction "3_3") (pintype "passive"))
      (node (ref "D4") (pin "A") (pinfunction "A_A") (pintype "passive"))
      (node (ref "Q5") (pin "3") (pinfunction "D_3") (pintype "bidirectional"))
      (node (ref "R24") (pin "2") (pinfunction "2_2") (pintype "passive"))
    )
    (net (code "58") (name "Net-(Q5-G)") (class "Default")
      (node (ref "Q5") (pin "1") (pinfunction "G_1") (pintype "bidirectional"))
      (node (ref "R20") (pin "2") (pinfunction "2_2") (pintype "passive"))
      (node (ref "R24") (pin "1") (pinfunction "1_1") (pintype "passive"))
    )
    (net (code "59") (name "Net-(U1C-PA4)") (class "Default")
      (node (ref "R1") (pin "1") (pinfunction "1_1") (pintype "passive"))
      (node (ref "U1") (pin "20") (pinfunction "PA4_20") (pintype "bidirectional"))
    )
    (net (code "60") (name "Net-(U1E-PB2)") (class "Default")
      (node (ref "R25") (pin "1") (pinfunction "1_1") (pintype "passive"))
      (node (ref "U1") (pin "28") (pinfunction "PB2_28") (pintype "bidirectional"))
    )
    (net (code "61") (name "Net-(U1F-PC10)") (class "Default")
      (node (ref "R21") (pin "1") (pinfunction "1_1") (pintype "passive"))
      (node (ref "U1") (pin "51") (pinfunction "PC10_51") (pintype "bidirectional"))
    )
    (net (code "62") (name "Net-(U1F-PC11)") (class "Default")
      (node (ref "R22") (pin "1") (pinfunction "1_1") (pintype "passive"))
      (node (ref "U1") (pin "52") (pinfunction "PC11_52") (pintype "bidirectional"))
    )
    (net (code "63") (name "Net-(U1F-PC14)") (class "Default")
      (node (ref "C5") (pin "1") (pinfunction "1_1") (pintype "passive"))
      (node (ref "U1") (pin "3") (pinfunction "PC14_3") (pintype "bidirectional"))
      (node (ref "Y1") (pin "1") (pinfunction "1_1") (pintype "passive"))
    )
    (net (code "64") (name "Net-(U1F-PC15)") (class "Default")
      (node (ref "C4") (pin "1") (pinfunction "1_1") (pintype "passive"))
      (node (ref "U1") (pin "4") (pinfunction "PC15_4") (pintype "bidirectional"))
      (node (ref "Y1") (pin "2") (pinfunction "2_2") (pintype "passive"))
    )
    (net (code "65") (name "Net-(U1H-PD0{slash}OSC<=)") (class "Default")
      (node (ref "C3") (pin "1") (pinfunction "1_1") (pintype "passive"))
      (node (ref "U1") (pin "5") (pinfunction "PD0/OSC<=_5") (pintype "bidirectional"))
      (node (ref "Y2") (pin "2") (pinfunction "2_2") (pintype "passive"))
    )
    (net (code "66") (name "Net-(U1H-PD1{slash}OSC=>)") (class "Default")
      (node (ref "C2") (pin "1") (pinfunction "1_1") (pintype "passive"))
      (node (ref "U1") (pin "6") (pinfunction "PD1/OSC=>_6") (pintype "bidirectional"))
      (node (ref "Y2") (pin "1") (pinfunction "1_1") (pintype "passive"))
    )
    (net (code "67") (name "Net-(U2-ISET)") (class "Default")
      (node (ref "R17") (pin "1") (pinfunction "1_1") (pintype "passive"))
      (node (ref "U2") (pin "2") (pinfunction "ISET_2") (pintype "input"))
    )
    (net (code "68") (name "Net-(U2-PRETERM)") (class "Default")
      (node (ref "R18") (pin "1") (pinfunction "1_1") (pintype "passive"))
      (node (ref "U2") (pin "4") (pinfunction "PRETERM_4") (pintype "input"))
    )
    (net (code "69") (name "Net-(U2-~{CHG})") (class "Default")
      (node (ref "D9") (pin "C") (pinfunction "C_C") (pintype "passive"))
      (node (ref "U2") (pin "8") (pinfunction "~{CHG}_8") (pintype "output"))
    )
    (net (code "70") (name "Net-(U2-~{PG})") (class "Default")
      (node (ref "D8") (pin "C") (pinfunction "C_C") (pintype "passive"))
      (node (ref "U2") (pin "5") (pinfunction "~{PG}_5") (pintype "output"))
    )
    (net (code "71") (name "Net-(U3-REGOUT)") (class "Default")
      (node (ref "C9") (pin "1") (pinfunction "1_1") (pintype "passive"))
      (node (ref "U3") (pin "10") (pinfunction "REGOUT_10") (pintype "bidirectional"))
      (node (ref "U5") (pin "10") (pinfunction "REGOUT_10") (pintype "bidirectional"))
    )
    (net (code "72") (name "Net-(U5-CPOUT)") (class "Default")
      (node (ref "C10") (pin "1") (pinfunction "1_1") (pintype "passive"))
      (node (ref "U5") (pin "20") (pinfunction "CPOUT_20") (pintype "bidirectional"))
    )
    (net (code "73") (name "V+") (class "Default")
      (node (ref "C11") (pin "1") (pinfunction "1_1") (pintype "passive"))
      (node (ref "C6") (pin "1") (pinfunction "1_1") (pintype "passive"))
      (node (ref "CN2") (pin "2") (pinfunction "2_2") (pintype "passive"))
      (node (ref "CN3") (pin "2") (pinfunction "2_2") (pintype "passive"))
      (node (ref "CN4") (pin "2") (pinfunction "2_2") (pintype "passive"))
      (node (ref "CN5") (pin "2") (pinfunction "2_2") (pintype "passive"))
      (node (ref "CN8") (pin "1") (pinfunction "1_1") (pintype "passive"))
      (node (ref "D1") (pin "C") (pinfunction "C_C") (pintype "passive"))
      (node (ref "D2") (pin "C") (pinfunction "C_C") (pintype "passive"))
      (node (ref "D3") (pin "C") (pinfunction "C_C") (pintype "passive"))
      (node (ref "D4") (pin "C") (pinfunction "C_C") (pintype "passive"))
      (node (ref "D5") (pin "C") (pinfunction "C_C") (pintype "passive"))
      (node (ref "R26") (pin "2") (pinfunction "2_2") (pintype "passive"))
      (node (ref "R27") (pin "2") (pinfunction "2_2") (pintype "passive"))
      (node (ref "R29") (pin "1") (pinfunction "1_1") (pintype "passive"))
      (node (ref "U2") (pin "10") (pinfunction "OUT_10") (pintype "output"))
      (node (ref "U6") (pin "1") (pinfunction "IN_1") (pintype "power_in"))
      (node (ref "U6") (pin "3") (pinfunction "EN_3") (pintype "input"))
    )
    (net (code "74") (name "unconnected-(U1B-PA8-Pad41)") (class "Default")
      (node (ref "U1") (pin "41") (pinfunction "PA8_41") (pintype "bidirectional"))
    )
    (net (code "75") (name "unconnected-(U1B-PA15-Pad50)") (class "Default")
      (node (ref "U1") (pin "50") (pinfunction "PA15_50") (pintype "bidirectional"))
    )
    (net (code "76") (name "unconnected-(U1E-PB3-Pad55)") (class "Default")
      (node (ref "U1") (pin "55") (pinfunction "PB3_55") (pintype "bidirectional"))
    )
    (net (code "77") (name "unconnected-(U1E-PB4-Pad56)") (class "Default")
      (node (ref "U1") (pin "56") (pinfunction "PB4_56") (pintype "bidirectional"))
    )
    (net (code "78") (name "unconnected-(U1E-PB5-Pad57)") (class "Default")
      (node (ref "U1") (pin "57") (pinfunction "PB5_57") (pintype "bidirectional"))
    )
    (net (code "79") (name "unconnected-(U1F-PC12-Pad53)") (class "Default")
      (node (ref "U1") (pin "53") (pinfunction "PC12_53") (pintype "bidirectional"))
    )
    (net (code "80") (name "unconnected-(U1F-PC13-Pad2)") (class "Default")
      (node (ref "U1") (pin "2") (pinfunction "PC13_2") (pintype "bidirectional"))
    )
    (net (code "81") (name "unconnected-(U1G-PC2-Pad10)") (class "Default")
      (node (ref "U1") (pin "10") (pinfunction "PC2_10") (pintype "bidirectional"))
    )
    (net (code "82") (name "unconnected-(U1G-PC4-Pad24)") (class "Default")
      (node (ref "U1") (pin "24") (pinfunction "PC4_24") (pintype "bidirectional"))
    )
    (net (code "83") (name "unconnected-(U1G-PC5-Pad25)") (class "Default")
      (node (ref "U1") (pin "25") (pinfunction "PC5_25") (pintype "bidirectional"))
    )
    (net (code "84") (name "unconnected-(U1H-PD2-Pad54)") (class "Default")
      (node (ref "U1") (pin "54") (pinfunction "PD2_54") (pintype "bidirectional"))
    )
    (net (code "85") (name "unconnected-(U2-EP-Pad11)") (class "Default")
      (node (ref "U2") (pin "11") (pinfunction "EP_11") (pintype "passive"))
    )
    (net (code "86") (name "unconnected-(U2-NC-Pad6)") (class "Default")
      (node (ref "U2") (pin "6") (pinfunction "NC_6") (pintype "no_connect"))
    )
    (net (code "87") (name "unconnected-(U3-AUX_CL-Pad7)") (class "Default")
      (node (ref "U3") (pin "7") (pinfunction "AUX_CL_7") (pintype "bidirectional"))
    )
    (net (code "88") (name "unconnected-(U3-AUX_DA-Pad21)") (class "Default")
      (node (ref "U3") (pin "21") (pinfunction "AUX_DA_21") (pintype "bidirectional"))
    )
    (net (code "89") (name "unconnected-(U4-VREF-Pad5)") (class "Default")
      (node (ref "U4") (pin "5") (pinfunction "VREF_5") (pintype "bidirectional"))
    )
    (net (code "90") (name "unconnected-(U5-AUXCL-Pad7)") (class "Default")
      (node (ref "U5") (pin "7") (pinfunction "AUXCL_7") (pintype "bidirectional"))
    )
    (net (code "91") (name "unconnected-(U5-AUXDA-Pad6)") (class "Default")
      (node (ref "U5") (pin "6") (pinfunction "AUXDA_6") (pintype "bidirectional"))
    )
    (net (code "92") (name "unconnected-(U5-CLKIN-Pad1)") (class "Default")
      (node (ref "U5") (pin "1") (pinfunction "CLKIN_1") (pintype "bidirectional"))
    )
    (net (code "93") (name "unconnected-(U5-CLKOUT-Pad22)") (class "Default")
      (node (ref "U5") (pin "22") (pinfunction "CLKOUT_22") (pintype "bidirectional"))
    )
    (net (code "94") (name "unconnected-(U6-NC-Pad4)") (class "Default")
      (node (ref "U6") (pin "4") (pinfunction "NC_4") (pintype "no_connect"))
    )
  )
)
